# ATmega16_RTD.net
KiCad netlist of a schematic drawn in Altium Designer
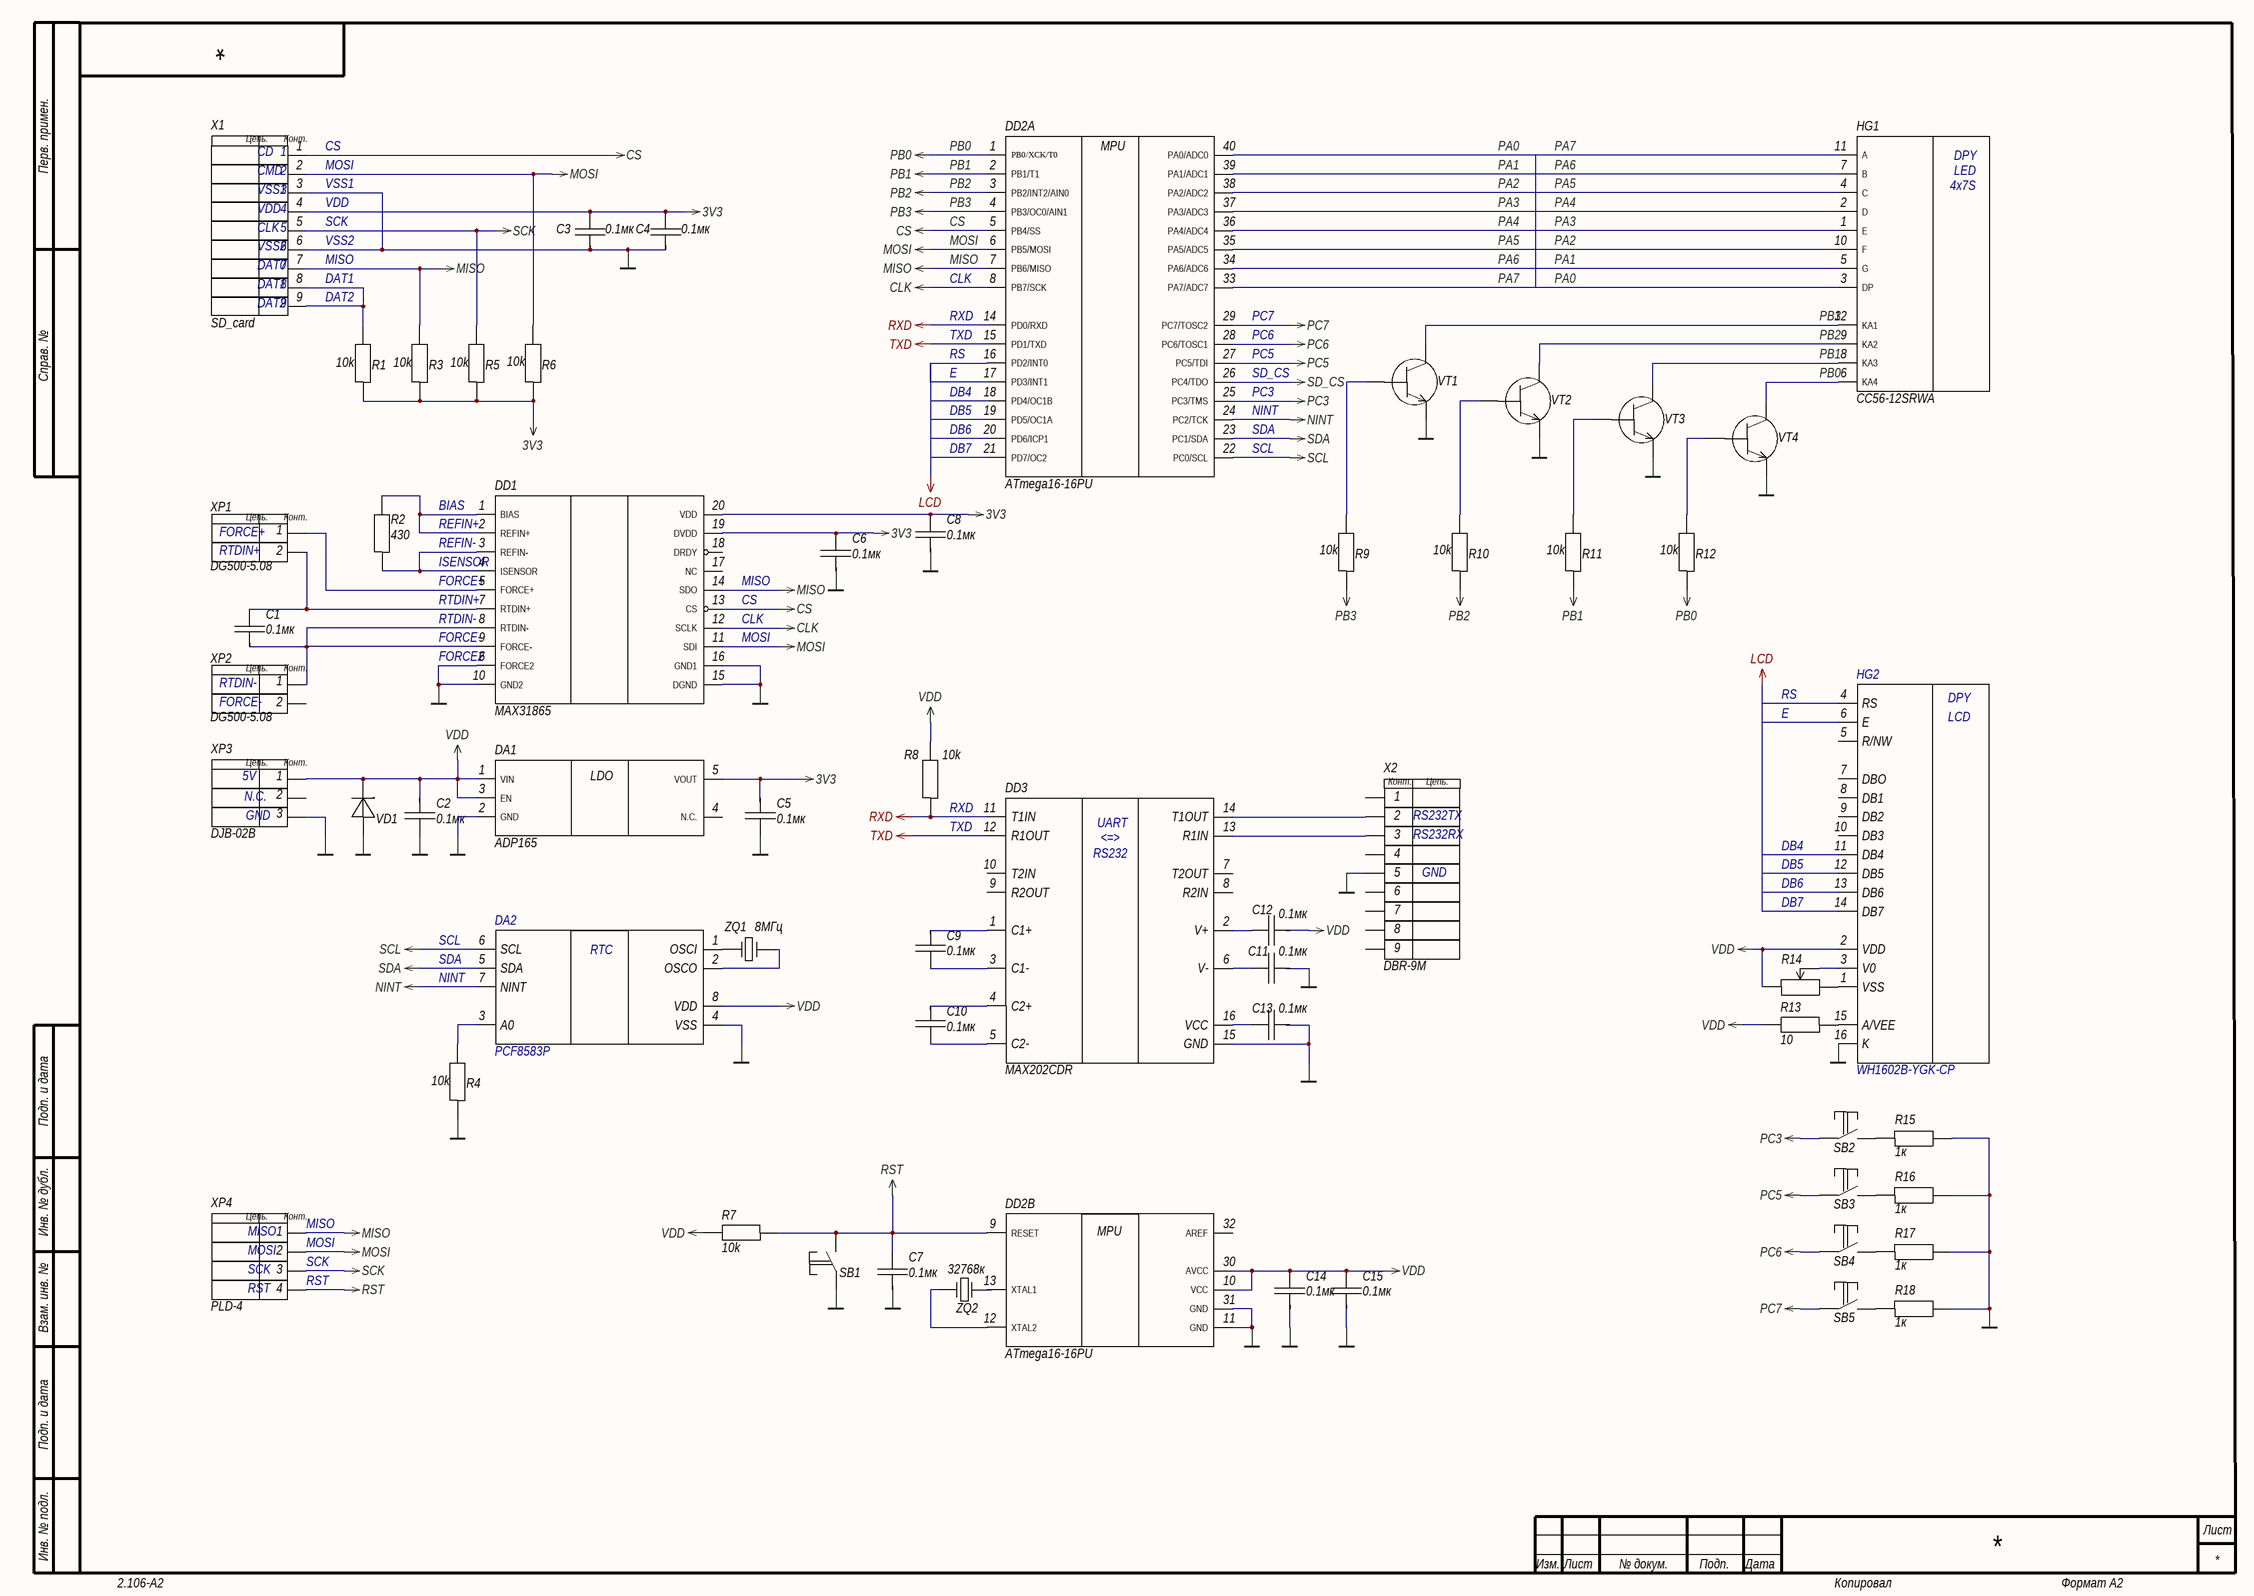
[diagram p0: ATmega16_RTD.SchDoc]

(export (version "E")
  (design (tool "Eeschema 10.0.6"))
  (components
    (comp (ref "C1")
      (value "0.1мк")
      (footprint "Capacitor")
      (libsource (lib "ATmega16_RTD") (part "Capacitor"))
    )
    (comp (ref "C2")
      (value "0.1мк")
      (footprint "Capacitor")
      (libsource (lib "ATmega16_RTD") (part "Capacitor"))
    )
    (comp (ref "C3")
      (value "0.1мк")
      (footprint "Capacitor")
      (libsource (lib "ATmega16_RTD") (part "Capacitor"))
    )
    (comp (ref "C4")
      (value "0.1мк")
      (footprint "Capacitor")
      (libsource (lib "ATmega16_RTD") (part "Capacitor"))
    )
    (comp (ref "C5")
      (value "0.1мк")
      (footprint "Capacitor")
      (libsource (lib "ATmega16_RTD") (part "Capacitor"))
    )
    (comp (ref "C6")
      (value "0.1мк")
      (footprint "Capacitor")
      (libsource (lib "ATmega16_RTD") (part "Capacitor"))
    )
    (comp (ref "C7")
      (value "0.1мк")
      (footprint "Capacitor")
      (libsource (lib "ATmega16_RTD") (part "Capacitor"))
    )
    (comp (ref "C8")
      (value "0.1мк")
      (footprint "Capacitor")
      (libsource (lib "ATmega16_RTD") (part "Capacitor"))
    )
    (comp (ref "C9")
      (value "0.1мк")
      (footprint "Capacitor")
      (libsource (lib "ATmega16_RTD") (part "Capacitor"))
    )
    (comp (ref "C10")
      (value "0.1мк")
      (footprint "Capacitor")
      (libsource (lib "ATmega16_RTD") (part "Capacitor"))
    )
    (comp (ref "C11")
      (value "0.1мк")
      (footprint "Capacitor")
      (libsource (lib "ATmega16_RTD") (part "Capacitor"))
    )
    (comp (ref "C12")
      (value "0.1мк")
      (footprint "Capacitor")
      (libsource (lib "ATmega16_RTD") (part "Capacitor"))
    )
    (comp (ref "C13")
      (value "0.1мк")
      (footprint "Capacitor")
      (libsource (lib "ATmega16_RTD") (part "Capacitor"))
    )
    (comp (ref "C14")
      (value "0.1мк")
      (footprint "Capacitor")
      (libsource (lib "ATmega16_RTD") (part "Capacitor"))
    )
    (comp (ref "C15")
      (value "0.1мк")
      (footprint "Capacitor")
      (libsource (lib "ATmega16_RTD") (part "Capacitor"))
    )
    (comp (ref "DA1") (value "ADP165") (libsource (lib "ATmega16_RTD") (part "LDO")))
    (comp (ref "DA2") (value "PCF8583P") (libsource (lib "ATmega16_RTD") (part "rtc")))
    (comp (ref "DD1") (value "MAX31865") (libsource (lib "ATmega16_RTD") (part "MAX 31856")))
    (comp (ref "DD2") (value "ATmega16-16PU") (libsource (lib "ATmega16_RTD") (part "ATMEGA 16")))
    (comp (ref "DD3") (value "MAX202CDR") (libsource (lib "ATmega16_RTD") (part "MAX_202")))
    (comp (ref "HG1") (value "CC56-12SRWA") (libsource (lib "ATmega16_RTD") (part "SevSeg_blok")))
    (comp (ref "HG2") (value "WH1602B-YGK-CP") (libsource (lib "ATmega16_RTD") (part "LCD")))
    (comp (ref "R1") (value "10k") (footprint "0603_RES") (libsource (lib "mikr_DZ1") (part "Resistor")))
    (comp (ref "R2") (value "430") (footprint "0603_RES") (libsource (lib "mikr_DZ1") (part "Resistor")))
    (comp (ref "R3") (value "10k") (footprint "0603_RES") (libsource (lib "mikr_DZ1") (part "Resistor")))
    (comp (ref "R4") (value "10k") (footprint "0603_RES") (libsource (lib "mikr_DZ1") (part "Resistor")))
    (comp (ref "R5") (value "10k") (footprint "0603_RES") (libsource (lib "mikr_DZ1") (part "Resistor")))
    (comp (ref "R6") (value "10k") (footprint "0603_RES") (libsource (lib "mikr_DZ1") (part "Resistor")))
    (comp (ref "R7") (value "10k") (footprint "0603_RES") (libsource (lib "mikr_DZ1") (part "Resistor")))
    (comp (ref "R8") (value "10k") (footprint "0603_RES") (libsource (lib "mikr_DZ1") (part "Resistor")))
    (comp (ref "R9") (value "10k") (footprint "0603_RES") (libsource (lib "mikr_DZ1") (part "Resistor")))
    (comp (ref "R10") (value "10k") (footprint "0603_RES") (libsource (lib "mikr_DZ1") (part "Resistor")))
    (comp (ref "R11") (value "10k") (footprint "0603_RES") (libsource (lib "mikr_DZ1") (part "Resistor")))
    (comp (ref "R12") (value "10k") (footprint "0603_RES") (libsource (lib "mikr_DZ1") (part "Resistor")))
    (comp (ref "R13") (value "10") (footprint "0603_RES") (libsource (lib "mikr_DZ1") (part "Resistor")))
    (comp (ref "R14")
      (value "~")
      (footprint "0603_RES")
      (libsource (lib "ATmega16_RTD") (part "Resistor_PEREM"))
    )
    (comp (ref "R15") (value "1к") (footprint "0603_RES") (libsource (lib "ATmega16_RTD") (part "Resistor")))
    (comp (ref "R16") (value "1к") (footprint "0603_RES") (libsource (lib "ATmega16_RTD") (part "Resistor")))
    (comp (ref "R17") (value "1к") (footprint "0603_RES") (libsource (lib "ATmega16_RTD") (part "Resistor")))
    (comp (ref "R18") (value "1к") (footprint "0603_RES") (libsource (lib "ATmega16_RTD") (part "Resistor")))
    (comp (ref "SB1")
      (value "2-1437565-7")
      (footprint "TACT_Switch")
      (libsource (lib "ATmega16_RTD") (part "Button"))
    )
    (comp (ref "SB2")
      (value "2-1437565-7")
      (footprint "TACT_Switch")
      (libsource (lib "ATmega16_RTD") (part "Button"))
    )
    (comp (ref "SB3")
      (value "2-1437565-7")
      (footprint "TACT_Switch")
      (libsource (lib "ATmega16_RTD") (part "Button"))
    )
    (comp (ref "SB4")
      (value "2-1437565-7")
      (footprint "TACT_Switch")
      (libsource (lib "ATmega16_RTD") (part "Button"))
    )
    (comp (ref "SB5")
      (value "2-1437565-7")
      (footprint "TACT_Switch")
      (libsource (lib "ATmega16_RTD") (part "Button"))
    )
    (comp (ref "VD1")
      (value "SS14-E3/61T")
      (footprint "SS14-E3/61T")
      (libsource (lib "ATmega16_RTD") (part "Diode"))
    )
    (comp (ref "VT1")
      (value "transistor_BC546_sevseg")
      (libsource (lib "mikr_DZ1") (part "transistor_BC546_sevseg"))
    )
    (comp (ref "VT2")
      (value "transistor_BC546_sevseg")
      (libsource (lib "mikr_DZ1") (part "transistor_BC546_sevseg"))
    )
    (comp (ref "VT3")
      (value "transistor_BC546_sevseg")
      (libsource (lib "mikr_DZ1") (part "transistor_BC546_sevseg"))
    )
    (comp (ref "VT4")
      (value "transistor_BC546_sevseg")
      (libsource (lib "mikr_DZ1") (part "transistor_BC546_sevseg"))
    )
    (comp (ref "X1") (value "SD_card") (libsource (lib "ATmega16_RTD") (part "SD_card")))
    (comp (ref "X2") (value "DBR-9M") (libsource (lib "ATmega16_RTD") (part "UART(RS-232)")))
    (comp (ref "XP1") (value "DG500-5.08") (libsource (lib "ATmega16_RTD") (part "Pt_100")))
    (comp (ref "XP2") (value "DG500-5.08") (libsource (lib "ATmega16_RTD") (part "Pt_100")))
    (comp (ref "XP3") (value "DJB-02B") (libsource (lib "ATmega16_RTD") (part "5V")))
    (comp (ref "XP4") (value "PLD-4") (libsource (lib "ATmega16_RTD") (part "SPI programer")))
    (comp (ref "ZQ1")
      (value "8МГц")
      (footprint "KX-KT 16.0 MHz")
      (libsource (lib "mikr_DZ1") (part "Quartz"))
    )
    (comp (ref "ZQ2")
      (value "32768к")
      (footprint "KX-KT 16.0 MHz")
      (libsource (lib "ATmega16_RTD") (part "Quartz"))
    )
  )
  (nets
    (net (code "1") (name "3V3") (class "Default")
      (node (ref "C3") (pin "1") (pinfunction "1_1") (pintype "passive"))
      (node (ref "C4") (pin "1") (pinfunction "1_1") (pintype "passive"))
      (node (ref "C5") (pin "2") (pinfunction "2_2") (pintype "passive"))
      (node (ref "C6") (pin "1") (pinfunction "1_1") (pintype "passive"))
      (node (ref "C8") (pin "1") (pinfunction "1_1") (pintype "passive"))
      (node (ref "DA1") (pin "5") (pinfunction "VOUT_5") (pintype "passive"))
      (node (ref "DD1") (pin "19") (pinfunction "DVDD_19") (pintype "passive"))
      (node (ref "DD1") (pin "20") (pinfunction "VDD_20") (pintype "passive"))
      (node (ref "R1") (pin "1") (pinfunction "GND_1") (pintype "passive"))
      (node (ref "R3") (pin "1") (pinfunction "GND_1") (pintype "passive"))
      (node (ref "R5") (pin "1") (pinfunction "GND_1") (pintype "passive"))
      (node (ref "R6") (pin "1") (pinfunction "GND_1") (pintype "passive"))
      (node (ref "X1") (pin "4") (pinfunction "VDD_4") (pintype "passive"))
    )
    (net (code "2") (name "CLK") (class "Default")
      (node (ref "DD1") (pin "12") (pinfunction "SCLK_12") (pintype "passive"))
      (node (ref "DD2") (pin "8") (pinfunction "PB7/SCK_8") (pintype "passive"))
    )
    (net (code "3") (name "CS") (class "Default")
      (node (ref "DD1") (pin "13") (pinfunction "CS_13") (pintype "passive"))
      (node (ref "DD2") (pin "5") (pinfunction "PB4/SS_5") (pintype "passive"))
      (node (ref "X1") (pin "1") (pinfunction "CD_1") (pintype "passive"))
    )
    (net (code "4") (name "GND") (class "Default")
      (node (ref "C11") (pin "2") (pinfunction "2_2") (pintype "passive"))
      (node (ref "C13") (pin "2") (pinfunction "2_2") (pintype "passive"))
      (node (ref "C14") (pin "2") (pinfunction "2_2") (pintype "passive"))
      (node (ref "C15") (pin "2") (pinfunction "2_2") (pintype "passive"))
      (node (ref "C2") (pin "1") (pinfunction "1_1") (pintype "passive"))
      (node (ref "C3") (pin "2") (pinfunction "2_2") (pintype "passive"))
      (node (ref "C4") (pin "2") (pinfunction "2_2") (pintype "passive"))
      (node (ref "C5") (pin "1") (pinfunction "1_1") (pintype "passive"))
      (node (ref "C6") (pin "2") (pinfunction "2_2") (pintype "passive"))
      (node (ref "C7") (pin "2") (pinfunction "2_2") (pintype "passive"))
      (node (ref "C8") (pin "2") (pinfunction "2_2") (pintype "passive"))
      (node (ref "DA1") (pin "2") (pinfunction "GND_2") (pintype "passive"))
      (node (ref "DA2") (pin "4") (pinfunction "VSS_4") (pintype "passive"))
      (node (ref "DD1") (pin "10") (pinfunction "GND2_10") (pintype "passive"))
      (node (ref "DD1") (pin "15") (pinfunction "DGND_15") (pintype "passive"))
      (node (ref "DD1") (pin "16") (pinfunction "GND1_16") (pintype "passive"))
      (node (ref "DD1") (pin "6") (pinfunction "FORCE2_6") (pintype "passive"))
      (node (ref "DD2") (pin "11") (pinfunction "GND_11") (pintype "passive"))
      (node (ref "DD2") (pin "31") (pinfunction "GND_31") (pintype "passive"))
      (node (ref "DD3") (pin "15") (pinfunction "GND_15") (pintype "passive"))
      (node (ref "HG2") (pin "16") (pinfunction "K_16") (pintype "passive"))
      (node (ref "R15") (pin "2") (pinfunction "GND_2") (pintype "passive"))
      (node (ref "R16") (pin "2") (pinfunction "GND_2") (pintype "passive"))
      (node (ref "R17") (pin "2") (pinfunction "GND_2") (pintype "passive"))
      (node (ref "R18") (pin "2") (pinfunction "GND_2") (pintype "passive"))
      (node (ref "R4") (pin "1") (pinfunction "GND_1") (pintype "passive"))
      (node (ref "SB1") (pin "1") (pinfunction "EP_1") (pintype "passive"))
      (node (ref "VD1") (pin "1") (pinfunction "GND_1") (pintype "passive"))
      (node (ref "VT1") (pin "Y118") (pinfunction "Y118_Y118") (pintype "passive"))
      (node (ref "VT2") (pin "Y118") (pinfunction "Y118_Y118") (pintype "passive"))
      (node (ref "VT3") (pin "Y118") (pinfunction "Y118_Y118") (pintype "passive"))
      (node (ref "VT4") (pin "Y118") (pinfunction "Y118_Y118") (pintype "passive"))
      (node (ref "X1") (pin "3") (pinfunction "VSS1_3") (pintype "passive"))
      (node (ref "X1") (pin "6") (pinfunction "VSS2_6") (pintype "passive"))
      (node (ref "X2") (pin "22") (pinfunction "GND_22") (pintype "passive"))
      (node (ref "XP3") (pin "GND") (pinfunction "GND_GND") (pintype "passive"))
    )
    (net (code "6") (name "MISO") (class "Default")
      (node (ref "DD1") (pin "14") (pinfunction "SDO_14") (pintype "passive"))
      (node (ref "DD2") (pin "7") (pinfunction "PB6/MISO_7") (pintype "passive"))
      (node (ref "R3") (pin "2") (pinfunction "GND_2") (pintype "passive"))
      (node (ref "X1") (pin "7") (pinfunction "DAT0_7") (pintype "passive"))
      (node (ref "XP4") (pin "Y124") (pinfunction "5V_Y124") (pintype "passive"))
    )
    (net (code "7") (name "MOSI") (class "Default")
      (node (ref "DD1") (pin "11") (pinfunction "SDI_11") (pintype "passive"))
      (node (ref "DD2") (pin "6") (pinfunction "PB5/MOSI_6") (pintype "passive"))
      (node (ref "R6") (pin "2") (pinfunction "GND_2") (pintype "passive"))
      (node (ref "X1") (pin "2") (pinfunction "CMD_2") (pintype "passive"))
      (node (ref "XP4") (pin "Y125") (pinfunction "NC_Y125") (pintype "passive"))
    )
    (net (code "8") (name "NINT") (class "Default")
      (node (ref "DA2") (pin "7") (pinfunction "NINT_7") (pintype "passive"))
      (node (ref "DD2") (pin "24") (pinfunction "PC2/TCK_24") (pintype "passive"))
    )
    (net (code "9") (name "Net-(DA2-A0)") (class "Default")
      (node (ref "DA2") (pin "3") (pinfunction "A0_3") (pintype "passive"))
      (node (ref "R4") (pin "2") (pinfunction "GND_2") (pintype "passive"))
    )
    (net (code "10") (name "Net-(DA2-OSCI)") (class "Default")
      (node (ref "DA2") (pin "1") (pinfunction "OSCI_1") (pintype "passive"))
      (node (ref "ZQ1") (pin "1") (pinfunction "EP_1") (pintype "passive"))
    )
    (net (code "11") (name "Net-(DA2-OSCO)") (class "Default")
      (node (ref "DA2") (pin "2") (pinfunction "OSCO_2") (pintype "passive"))
      (node (ref "ZQ1") (pin "2") (pinfunction "EP_2") (pintype "passive"))
    )
    (net (code "12") (name "Net-(DD1-BIAS)") (class "Default")
      (node (ref "DD1") (pin "1") (pinfunction "BIAS_1") (pintype "passive"))
      (node (ref "DD1") (pin "2") (pinfunction "REFIN+_2") (pintype "passive"))
      (node (ref "R2") (pin "2") (pinfunction "GND_2") (pintype "passive"))
    )
    (net (code "13") (name "Net-(DD1-FORCE+)") (class "Default")
      (node (ref "DD1") (pin "5") (pinfunction "FORCE+_5") (pintype "passive"))
      (node (ref "XP1") (pin "4") (pinfunction "4_4") (pintype "passive"))
    )
    (net (code "14") (name "Net-(DD1-FORCE-)") (class "Default")
      (node (ref "C1") (pin "2") (pinfunction "2_2") (pintype "passive"))
      (node (ref "DD1") (pin "8") (pinfunction "RTDIN-_8") (pintype "passive"))
      (node (ref "DD1") (pin "9") (pinfunction "FORCE-_9") (pintype "passive"))
      (node (ref "XP2") (pin "4") (pinfunction "4_4") (pintype "passive"))
    )
    (net (code "15") (name "Net-(DD1-ISENSOR)") (class "Default")
      (node (ref "DD1") (pin "3") (pinfunction "REFIN-_3") (pintype "passive"))
      (node (ref "DD1") (pin "4") (pinfunction "ISENSOR_4") (pintype "passive"))
      (node (ref "R2") (pin "1") (pinfunction "GND_1") (pintype "passive"))
    )
    (net (code "16") (name "Net-(DD1-RTDIN+)") (class "Default")
      (node (ref "C1") (pin "1") (pinfunction "1_1") (pintype "passive"))
      (node (ref "DD1") (pin "7") (pinfunction "RTDIN+_7") (pintype "passive"))
      (node (ref "XP1") (pin "5") (pinfunction "5_5") (pintype "passive"))
    )
    (net (code "17") (name "Net-(DD2A-PA0{slash}ADC0)") (class "Default")
      (node (ref "DD2") (pin "40") (pinfunction "PA0/ADC0_40") (pintype "passive"))
      (node (ref "HG1") (pin "11") (pinfunction "A_11") (pintype "passive"))
    )
    (net (code "18") (name "Net-(DD2A-PA1{slash}ADC1)") (class "Default")
      (node (ref "DD2") (pin "39") (pinfunction "PA1/ADC1_39") (pintype "passive"))
      (node (ref "HG1") (pin "7") (pinfunction "B_7") (pintype "passive"))
    )
    (net (code "19") (name "Net-(DD2A-PA2{slash}ADC2)") (class "Default")
      (node (ref "DD2") (pin "38") (pinfunction "PA2/ADC2_38") (pintype "passive"))
      (node (ref "HG1") (pin "4") (pinfunction "C_4") (pintype "passive"))
    )
    (net (code "20") (name "Net-(DD2A-PA3{slash}ADC3)") (class "Default")
      (node (ref "DD2") (pin "37") (pinfunction "PA3/ADC3_37") (pintype "passive"))
      (node (ref "HG1") (pin "2") (pinfunction "D_2") (pintype "passive"))
    )
    (net (code "21") (name "Net-(DD2A-PA4{slash}ADC4)") (class "Default")
      (node (ref "DD2") (pin "36") (pinfunction "PA4/ADC4_36") (pintype "passive"))
      (node (ref "HG1") (pin "1") (pinfunction "E_1") (pintype "passive"))
    )
    (net (code "22") (name "Net-(DD2A-PA5{slash}ADC5)") (class "Default")
      (node (ref "DD2") (pin "35") (pinfunction "PA5/ADC5_35") (pintype "passive"))
      (node (ref "HG1") (pin "10") (pinfunction "F_10") (pintype "passive"))
    )
    (net (code "23") (name "Net-(DD2A-PA6{slash}ADC6)") (class "Default")
      (node (ref "DD2") (pin "34") (pinfunction "PA6/ADC6_34") (pintype "passive"))
      (node (ref "HG1") (pin "5") (pinfunction "G_5") (pintype "passive"))
    )
    (net (code "24") (name "Net-(DD2A-PA7{slash}ADC7)") (class "Default")
      (node (ref "DD2") (pin "33") (pinfunction "PA7/ADC7_33") (pintype "passive"))
      (node (ref "HG1") (pin "3") (pinfunction "DP_3") (pintype "passive"))
    )
    (net (code "25") (name "Net-(DD2A-PD2{slash}INT0)") (class "Default")
      (node (ref "DD2") (pin "16") (pinfunction "PD2/INT0_16") (pintype "passive"))
      (node (ref "DD2") (pin "17") (pinfunction "PD3/INT1_17") (pintype "passive"))
    )
    (net (code "26") (name "Net-(DD2B-XTAL1)") (class "Default")
      (node (ref "DD2") (pin "13") (pinfunction "XTAL1_13") (pintype "passive"))
      (node (ref "ZQ2") (pin "1") (pinfunction "EP_1") (pintype "passive"))
    )
    (net (code "27") (name "Net-(DD2B-XTAL2)") (class "Default")
      (node (ref "DD2") (pin "12") (pinfunction "XTAL2_12") (pintype "passive"))
      (node (ref "ZQ2") (pin "2") (pinfunction "EP_2") (pintype "passive"))
    )
    (net (code "28") (name "Net-(DD3-C1+)") (class "Default")
      (node (ref "C9") (pin "2") (pinfunction "2_2") (pintype "passive"))
      (node (ref "DD3") (pin "1") (pinfunction "C1+_1") (pintype "passive"))
    )
    (net (code "29") (name "Net-(DD3-C1-)") (class "Default")
      (node (ref "C9") (pin "1") (pinfunction "1_1") (pintype "passive"))
      (node (ref "DD3") (pin "3") (pinfunction "C1-_3") (pintype "passive"))
    )
    (net (code "30") (name "Net-(DD3-C2+)") (class "Default")
      (node (ref "C10") (pin "2") (pinfunction "2_2") (pintype "passive"))
      (node (ref "DD3") (pin "4") (pinfunction "C2+_4") (pintype "passive"))
    )
    (net (code "31") (name "Net-(DD3-C2-)") (class "Default")
      (node (ref "C10") (pin "1") (pinfunction "1_1") (pintype "passive"))
      (node (ref "DD3") (pin "5") (pinfunction "C2-_5") (pintype "passive"))
    )
    (net (code "32") (name "Net-(DD3-R1IN)") (class "Default")
      (node (ref "DD3") (pin "13") (pinfunction "R1IN_13") (pintype "passive"))
      (node (ref "X2") (pin "20") (pinfunction "GND_20") (pintype "passive"))
    )
    (net (code "33") (name "Net-(DD3-T1OUT)") (class "Default")
      (node (ref "DD3") (pin "14") (pinfunction "T1OUT_14") (pintype "passive"))
      (node (ref "X2") (pin "19") (pinfunction "GND_19") (pintype "passive"))
    )
    (net (code "34") (name "Net-(DD3-V+)") (class "Default")
      (node (ref "C12") (pin "1") (pinfunction "1_1") (pintype "passive"))
      (node (ref "DD3") (pin "2") (pinfunction "V+_2") (pintype "passive"))
    )
    (net (code "35") (name "Net-(DD3-V-)") (class "Default")
      (node (ref "C11") (pin "1") (pinfunction "1_1") (pintype "passive"))
      (node (ref "DD3") (pin "6") (pinfunction "V-_6") (pintype "passive"))
    )
    (net (code "36") (name "Net-(DD3-VCC)") (class "Default")
      (node (ref "C13") (pin "1") (pinfunction "1_1") (pintype "passive"))
      (node (ref "DD3") (pin "16") (pinfunction "VCC_16") (pintype "passive"))
    )
    (net (code "37") (name "Net-(HG1-KA1)") (class "Default")
      (node (ref "HG1") (pin "12") (pinfunction "KA1_12") (pintype "passive"))
      (node (ref "VT1") (pin "Y117") (pinfunction "Y117_Y117") (pintype "passive"))
    )
    (net (code "38") (name "Net-(HG1-KA2)") (class "Default")
      (node (ref "HG1") (pin "9") (pinfunction "KA2_9") (pintype "passive"))
      (node (ref "VT2") (pin "Y117") (pinfunction "Y117_Y117") (pintype "passive"))
    )
    (net (code "39") (name "Net-(HG1-KA3)") (class "Default")
      (node (ref "HG1") (pin "8") (pinfunction "KA3_8") (pintype "passive"))
      (node (ref "VT3") (pin "Y117") (pinfunction "Y117_Y117") (pintype "passive"))
    )
    (net (code "40") (name "Net-(HG1-KA4)") (class "Default")
      (node (ref "HG1") (pin "6") (pinfunction "KA4_6") (pintype "passive"))
      (node (ref "VT4") (pin "Y117") (pinfunction "Y117_Y117") (pintype "passive"))
    )
    (net (code "41") (name "Net-(HG2-A{slash}VEE)") (class "Default")
      (node (ref "HG2") (pin "15") (pinfunction "A/VEE_15") (pintype "passive"))
      (node (ref "R13") (pin "1") (pinfunction "GND_1") (pintype "passive"))
    )
    (net (code "42") (name "Net-(HG2-V0)") (class "Default")
      (node (ref "HG2") (pin "3") (pinfunction "V0_3") (pintype "passive"))
      (node (ref "R14") (pin "3") (pinfunction "3_3") (pintype "passive"))
    )
    (net (code "43") (name "Net-(HG2-VSS)") (class "Default")
      (node (ref "HG2") (pin "1") (pinfunction "VSS_1") (pintype "passive"))
      (node (ref "R14") (pin "2") (pinfunction "GND_2") (pintype "passive"))
    )
    (net (code "44") (name "Net-(R9-GND-Pad2)") (class "Default")
      (node (ref "R9") (pin "2") (pinfunction "GND_2") (pintype "passive"))
      (node (ref "VT1") (pin "Y116") (pinfunction "Y116_Y116") (pintype "passive"))
    )
    (net (code "45") (name "Net-(R10-GND-Pad2)") (class "Default")
      (node (ref "R10") (pin "2") (pinfunction "GND_2") (pintype "passive"))
      (node (ref "VT2") (pin "Y116") (pinfunction "Y116_Y116") (pintype "passive"))
    )
    (net (code "46") (name "Net-(R11-GND-Pad2)") (class "Default")
      (node (ref "R11") (pin "2") (pinfunction "GND_2") (pintype "passive"))
      (node (ref "VT3") (pin "Y116") (pinfunction "Y116_Y116") (pintype "passive"))
    )
    (net (code "47") (name "Net-(R12-GND-Pad2)") (class "Default")
      (node (ref "R12") (pin "2") (pinfunction "GND_2") (pintype "passive"))
      (node (ref "VT4") (pin "Y116") (pinfunction "Y116_Y116") (pintype "passive"))
    )
    (net (code "48") (name "Net-(R15-GND-Pad1)") (class "Default")
      (node (ref "R15") (pin "1") (pinfunction "GND_1") (pintype "passive"))
      (node (ref "SB2") (pin "2") (pinfunction "EP_2") (pintype "passive"))
    )
    (net (code "49") (name "Net-(R16-GND-Pad1)") (class "Default")
      (node (ref "R16") (pin "1") (pinfunction "GND_1") (pintype "passive"))
      (node (ref "SB3") (pin "2") (pinfunction "EP_2") (pintype "passive"))
    )
    (net (code "50") (name "Net-(R17-GND-Pad1)") (class "Default")
      (node (ref "R17") (pin "1") (pinfunction "GND_1") (pintype "passive"))
      (node (ref "SB4") (pin "2") (pinfunction "EP_2") (pintype "passive"))
    )
    (net (code "51") (name "Net-(R18-GND-Pad1)") (class "Default")
      (node (ref "R18") (pin "1") (pinfunction "GND_1") (pintype "passive"))
      (node (ref "SB5") (pin "2") (pinfunction "EP_2") (pintype "passive"))
    )
    (net (code "52") (name "Net-(X1-DAT1)") (class "Default")
      (node (ref "R1") (pin "2") (pinfunction "GND_2") (pintype "passive"))
      (node (ref "X1") (pin "8") (pinfunction "DAT1_8") (pintype "passive"))
      (node (ref "X1") (pin "9") (pinfunction "DAT2_9") (pintype "passive"))
    )
    (net (code "53") (name "PB0") (class "Default")
      (node (ref "DD2") (pin "1") (pinfunction "PB0/XCK/T0_1") (pintype "passive"))
      (node (ref "R12") (pin "1") (pinfunction "GND_1") (pintype "passive"))
    )
    (net (code "54") (name "PB1") (class "Default")
      (node (ref "DD2") (pin "2") (pinfunction "PB1/T1_2") (pintype "passive"))
      (node (ref "R11") (pin "1") (pinfunction "GND_1") (pintype "passive"))
    )
    (net (code "55") (name "PB2") (class "Default")
      (node (ref "DD2") (pin "3") (pinfunction "PB2/INT2/AIN0_3") (pintype "passive"))
      (node (ref "R10") (pin "1") (pinfunction "GND_1") (pintype "passive"))
    )
    (net (code "56") (name "PB3") (class "Default")
      (node (ref "DD2") (pin "4") (pinfunction "PB3/OC0/AIN1_4") (pintype "passive"))
      (node (ref "R9") (pin "1") (pinfunction "GND_1") (pintype "passive"))
    )
    (net (code "57") (name "PC3") (class "Default")
      (node (ref "DD2") (pin "25") (pinfunction "PC3/TMS_25") (pintype "passive"))
      (node (ref "SB2") (pin "1") (pinfunction "EP_1") (pintype "passive"))
    )
    (net (code "58") (name "PC5") (class "Default")
      (node (ref "DD2") (pin "27") (pinfunction "PC5/TDI_27") (pintype "passive"))
      (node (ref "SB3") (pin "1") (pinfunction "EP_1") (pintype "passive"))
    )
    (net (code "59") (name "PC6") (class "Default")
      (node (ref "DD2") (pin "28") (pinfunction "PC6/TOSC1_28") (pintype "passive"))
      (node (ref "SB4") (pin "1") (pinfunction "EP_1") (pintype "passive"))
    )
    (net (code "60") (name "PC7") (class "Default")
      (node (ref "DD2") (pin "29") (pinfunction "PC7/TOSC2_29") (pintype "passive"))
      (node (ref "SB5") (pin "1") (pinfunction "EP_1") (pintype "passive"))
    )
    (net (code "61") (name "RST") (class "Default")
      (node (ref "C7") (pin "1") (pinfunction "1_1") (pintype "passive"))
      (node (ref "DD2") (pin "9") (pinfunction "RESET_9") (pintype "passive"))
      (node (ref "R7") (pin "1") (pinfunction "GND_1") (pintype "passive"))
      (node (ref "SB1") (pin "2") (pinfunction "EP_2") (pintype "passive"))
      (node (ref "XP4") (pin "GND") (pinfunction "GND_GND") (pintype "passive"))
    )
    (net (code "62") (name "RXD") (class "Default")
      (node (ref "DD2") (pin "14") (pinfunction "PD0/RXD_14") (pintype "passive"))
      (node (ref "DD3") (pin "11") (pinfunction "T1IN_11") (pintype "passive"))
      (node (ref "R8") (pin "1") (pinfunction "GND_1") (pintype "passive"))
    )
    (net (code "63") (name "SCK") (class "Default")
      (node (ref "R5") (pin "2") (pinfunction "GND_2") (pintype "passive"))
      (node (ref "X1") (pin "5") (pinfunction "CLK_5") (pintype "passive"))
      (node (ref "XP4") (pin "GND") (pinfunction "GND_GND") (pintype "passive"))
    )
    (net (code "64") (name "SCL") (class "Default")
      (node (ref "DA2") (pin "6") (pinfunction "SCL_6") (pintype "passive"))
      (node (ref "DD2") (pin "22") (pinfunction "PC0/SCL_22") (pintype "passive"))
    )
    (net (code "65") (name "SDA") (class "Default")
      (node (ref "DA2") (pin "5") (pinfunction "SDA_5") (pintype "passive"))
      (node (ref "DD2") (pin "23") (pinfunction "PC1/SDA_23") (pintype "passive"))
    )
    (net (code "66") (name "SD_CS") (class "Default")
      (node (ref "DD2") (pin "26") (pinfunction "PC4/TDO_26") (pintype "passive"))
    )
    (net (code "67") (name "TXD") (class "Default")
      (node (ref "DD2") (pin "15") (pinfunction "PD1/TXD_15") (pintype "passive"))
      (node (ref "DD3") (pin "12") (pinfunction "R1OUT_12") (pintype "passive"))
    )
    (net (code "68") (name "VDD") (class "Default")
      (node (ref "C12") (pin "2") (pinfunction "2_2") (pintype "passive"))
      (node (ref "C14") (pin "1") (pinfunction "1_1") (pintype "passive"))
      (node (ref "C15") (pin "1") (pinfunction "1_1") (pintype "passive"))
      (node (ref "C2") (pin "2") (pinfunction "2_2") (pintype "passive"))
      (node (ref "DA1") (pin "1") (pinfunction "VIN_1") (pintype "passive"))
      (node (ref "DA1") (pin "3") (pinfunction "EN_3") (pintype "passive"))
      (node (ref "DA2") (pin "8") (pinfunction "VDD_8") (pintype "passive"))
      (node (ref "DD2") (pin "10") (pinfunction "VCC_10") (pintype "passive"))
      (node (ref "DD2") (pin "30") (pinfunction "AVCC_30") (pintype "passive"))
      (node (ref "HG2") (pin "2") (pinfunction "VDD_2") (pintype "passive"))
      (node (ref "R13") (pin "2") (pinfunction "GND_2") (pintype "passive"))
      (node (ref "R14") (pin "1") (pinfunction "GND_1") (pintype "passive"))
      (node (ref "R7") (pin "2") (pinfunction "GND_2") (pintype "passive"))
      (node (ref "R8") (pin "2") (pinfunction "GND_2") (pintype "passive"))
      (node (ref "VD1") (pin "2") (pinfunction "GND_2") (pintype "passive"))
      (node (ref "XP3") (pin "Y124") (pinfunction "5V_Y124") (pintype "passive"))
    )
    (net (code "69") (name "unconnected-(DA1-N.C.-Pad4)") (class "Default")
      (node (ref "DA1") (pin "4") (pinfunction "N.C._4") (pintype "passive"))
    )
    (net (code "70") (name "unconnected-(DD1-DRDY-Pad18)") (class "Default")
      (node (ref "DD1") (pin "18") (pinfunction "DRDY_18") (pintype "passive"))
    )
    (net (code "71") (name "unconnected-(DD1-NC-Pad17)") (class "Default")
      (node (ref "DD1") (pin "17") (pinfunction "NC_17") (pintype "passive"))
    )
    (net (code "72") (name "unconnected-(DD2A-PD4{slash}OC1B-Pad18)") (class "Default")
      (node (ref "DD2") (pin "18") (pinfunction "PD4/OC1B_18") (pintype "passive"))
    )
    (net (code "73") (name "unconnected-(DD2A-PD5{slash}OC1A-Pad19)") (class "Default")
      (node (ref "DD2") (pin "19") (pinfunction "PD5/OC1A_19") (pintype "passive"))
    )
    (net (code "74") (name "unconnected-(DD2A-PD6{slash}ICP1-Pad20)") (class "Default")
      (node (ref "DD2") (pin "20") (pinfunction "PD6/ICP1_20") (pintype "passive"))
    )
    (net (code "75") (name "unconnected-(DD2A-PD7{slash}OC2-Pad21)") (class "Default")
      (node (ref "DD2") (pin "21") (pinfunction "PD7/OC2_21") (pintype "passive"))
    )
    (net (code "76") (name "unconnected-(DD2B-AREF-Pad32)") (class "Default")
      (node (ref "DD2") (pin "32") (pinfunction "AREF_32") (pintype "passive"))
    )
    (net (code "77") (name "unconnected-(DD3-R2IN-Pad8)") (class "Default")
      (node (ref "DD3") (pin "8") (pinfunction "R2IN_8") (pintype "passive"))
    )
    (net (code "78") (name "unconnected-(DD3-R2OUT-Pad9)") (class "Default")
      (node (ref "DD3") (pin "9") (pinfunction "R2OUT_9") (pintype "passive"))
    )
    (net (code "79") (name "unconnected-(DD3-T2IN-Pad10)") (class "Default")
      (node (ref "DD3") (pin "10") (pinfunction "T2IN_10") (pintype "passive"))
    )
    (net (code "80") (name "unconnected-(DD3-T2OUT-Pad7)") (class "Default")
      (node (ref "DD3") (pin "7") (pinfunction "T2OUT_7") (pintype "passive"))
    )
    (net (code "81") (name "unconnected-(HG2-DB1-Pad8)") (class "Default")
      (node (ref "HG2") (pin "8") (pinfunction "DB1_8") (pintype "passive"))
    )
    (net (code "82") (name "unconnected-(HG2-DB2-Pad9)") (class "Default")
      (node (ref "HG2") (pin "9") (pinfunction "DB2_9") (pintype "passive"))
    )
    (net (code "83") (name "unconnected-(HG2-DB3-Pad10)") (class "Default")
      (node (ref "HG2") (pin "10") (pinfunction "DB3_10") (pintype "passive"))
    )
    (net (code "84") (name "unconnected-(HG2-DB4-Pad11)") (class "Default")
      (node (ref "HG2") (pin "11") (pinfunction "DB4_11") (pintype "passive"))
    )
    (net (code "85") (name "unconnected-(HG2-DB5-Pad12)") (class "Default")
      (node (ref "HG2") (pin "12") (pinfunction "DB5_12") (pintype "passive"))
    )
    (net (code "86") (name "unconnected-(HG2-DB6-Pad13)") (class "Default")
      (node (ref "HG2") (pin "13") (pinfunction "DB6_13") (pintype "passive"))
    )
    (net (code "87") (name "unconnected-(HG2-DB7-Pad14)") (class "Default")
      (node (ref "HG2") (pin "14") (pinfunction "DB7_14") (pintype "passive"))
    )
    (net (code "88") (name "unconnected-(HG2-DBO-Pad7)") (class "Default")
      (node (ref "HG2") (pin "7") (pinfunction "DBO_7") (pintype "passive"))
    )
    (net (code "89") (name "unconnected-(HG2-E-Pad6)") (class "Default")
      (node (ref "HG2") (pin "6") (pinfunction "E_6") (pintype "passive"))
    )
    (net (code "90") (name "unconnected-(HG2-RS-Pad4)") (class "Default")
      (node (ref "HG2") (pin "4") (pinfunction "RS_4") (pintype "passive"))
    )
    (net (code "91") (name "unconnected-(HG2-R{slash}NW-Pad5)") (class "Default")
      (node (ref "HG2") (pin "5") (pinfunction "R/NW_5") (pintype "passive"))
    )
    (net (code "92") (name "unconnected-(X2-GND-Pad18)") (class "Default")
      (node (ref "X2") (pin "18") (pinfunction "GND_18") (pintype "passive"))
    )
    (net (code "93") (name "unconnected-(X2-GND-Pad21)") (class "Default")
      (node (ref "X2") (pin "21") (pinfunction "GND_21") (pintype "passive"))
    )
    (net (code "94") (name "unconnected-(X2-GND-Pad23)") (class "Default")
      (node (ref "X2") (pin "23") (pinfunction "GND_23") (pintype "passive"))
    )
    (net (code "95") (name "unconnected-(X2-GND-Pad24)") (class "Default")
      (node (ref "X2") (pin "24") (pinfunction "GND_24") (pintype "passive"))
    )
    (net (code "96") (name "unconnected-(X2-GND-Pad25)") (class "Default")
      (node (ref "X2") (pin "25") (pinfunction "GND_25") (pintype "passive"))
    )
    (net (code "97") (name "unconnected-(X2-GND-Pad26)") (class "Default")
      (node (ref "X2") (pin "26") (pinfunction "GND_26") (pintype "passive"))
    )
    (net (code "98") (name "unconnected-(XP2-Pad5)") (class "Default")
      (node (ref "XP2") (pin "5") (pinfunction "5_5") (pintype "passive"))
    )
    (net (code "99") (name "unconnected-(XP3-NC-PadY125)") (class "Default")
      (node (ref "XP3") (pin "Y125") (pinfunction "NC_Y125") (pintype "passive"))
    )
  )
)
